# VT_12S_LHS_V0_1.net
KiCad netlist of a schematic drawn in Altium Designer
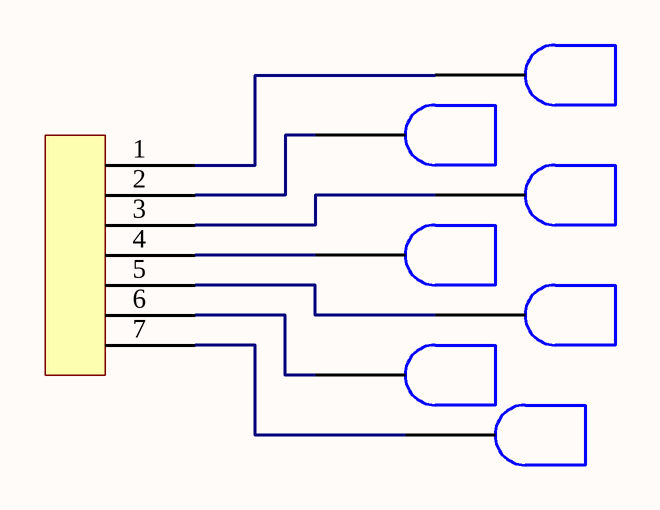
[diagram p0: VT 12S LHS V0.1.SchDoc]

(export (version "E")
  (design (tool "Eeschema 10.0.6"))
  (components
    (comp (ref "J1")
      (value "Voltage Tap")
      (footprint "Voltage Tap")
      (libsource (lib "Voltage Taps V0.1") (part "Voltage Tap"))
    )
    (comp (ref "J2")
      (value "Voltage Tap")
      (footprint "Voltage Tap")
      (libsource (lib "Voltage Taps V0.1") (part "Voltage Tap"))
    )
    (comp (ref "J3")
      (value "Voltage Tap")
      (footprint "Voltage Tap")
      (libsource (lib "Voltage Taps V0.1") (part "Voltage Tap"))
    )
    (comp (ref "J4")
      (value "Voltage Tap")
      (footprint "Voltage Tap")
      (libsource (lib "Voltage Taps V0.1") (part "Voltage Tap"))
    )
    (comp (ref "J5")
      (value "Voltage Tap")
      (footprint "Voltage Tap")
      (libsource (lib "Voltage Taps V0.1") (part "Voltage Tap"))
    )
    (comp (ref "J6")
      (value "84953-7-FPC")
      (footprint "84953-7 - FPC")
      (description "FPC Connectors, Flex-to-Board, 7 Position, .039 in [1 mm] Centerline, FPC Side Connector")
      (libsource (lib "TE_Con") (part "84953-7-FPC"))
    )
    (comp (ref "J7")
      (value "Voltage Tap")
      (footprint "Voltage Tap")
      (libsource (lib "Voltage Taps V0.1") (part "Voltage Tap"))
    )
    (comp (ref "J8")
      (value "Voltage Tap")
      (footprint "Voltage Tap")
      (libsource (lib "Voltage Taps V0.1") (part "Voltage Tap"))
    )
  )
  (nets
    (net (code "1") (name "Net-(J1-Pad1)") (class "Default")
      (node (ref "J1") (pin "1") (pintype "passive"))
      (node (ref "J6") (pin "1") (pintype "passive"))
    )
    (net (code "2") (name "Net-(J2-Pad1)") (class "Default")
      (node (ref "J2") (pin "1") (pintype "passive"))
      (node (ref "J6") (pin "2") (pintype "passive"))
    )
    (net (code "3") (name "Net-(J3-Pad1)") (class "Default")
      (node (ref "J3") (pin "1") (pintype "passive"))
      (node (ref "J6") (pin "3") (pintype "passive"))
    )
    (net (code "4") (name "Net-(J4-Pad1)") (class "Default")
      (node (ref "J4") (pin "1") (pintype "passive"))
      (node (ref "J6") (pin "4") (pintype "passive"))
    )
    (net (code "5") (name "Net-(J5-Pad1)") (class "Default")
      (node (ref "J5") (pin "1") (pintype "passive"))
      (node (ref "J6") (pin "5") (pintype "passive"))
    )
    (net (code "6") (name "Net-(J6-Pad6)") (class "Default")
      (node (ref "J6") (pin "6") (pintype "passive"))
      (node (ref "J7") (pin "1") (pintype "passive"))
    )
    (net (code "7") (name "Net-(J6-Pad7)") (class "Default")
      (node (ref "J6") (pin "7") (pintype "passive"))
      (node (ref "J8") (pin "1") (pintype "passive"))
    )
  )
)
